# 4_-MCU_POWER.net
KiCad netlist of a schematic drawn in Altium Designer
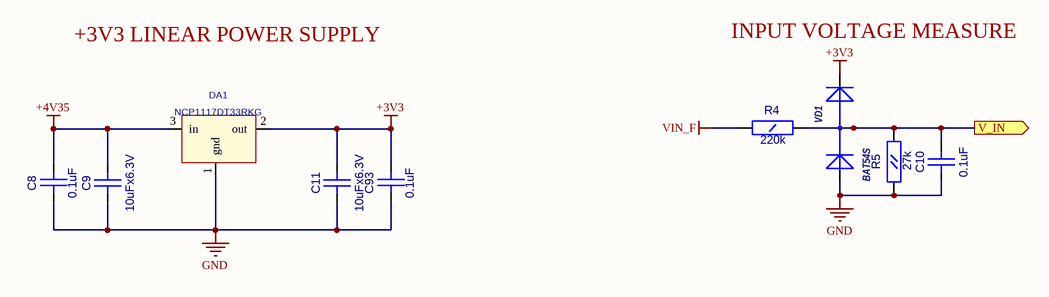
[diagram p0: [4]-MCU_POWER.SchDoc]

(export (version "E")
  (design (tool "Eeschema 10.0.6"))
  (components
    (comp (ref "C8")
      (value "0.1uF")
      (footprint "CC0603")
      (description "CC0603")
      (libsource (lib "gprs_modem_2") (part "CC0603"))
    )
    (comp (ref "C9")
      (value "10uFx6.3V")
      (footprint "CC0805")
      (description "CC0805")
      (libsource (lib "gprs_modem_2") (part "CC0805"))
    )
    (comp (ref "C10")
      (value "0.1uF")
      (footprint "CC0603")
      (description "CC0603")
      (libsource (lib "gprs_modem_2") (part "CC0603"))
    )
    (comp (ref "C11")
      (value "10uFx6.3V")
      (footprint "CC0805")
      (description "CC0805")
      (libsource (lib "gprs_modem_2") (part "CC0805"))
    )
    (comp (ref "C93")
      (value "0.1uF")
      (footprint "CC0603")
      (description "CC0603")
      (libsource (lib "gprs_modem_2") (part "CC0603"))
    )
    (comp (ref "DA1")
      (value "NCP1117DT33RKG")
      (footprint "SOT-223")
      (description "Linear Regulator 3.3V")
      (libsource (lib "fizik_lib") (part "NCP1117DT33RKG"))
    )
    (comp (ref "R4")
      (value "220k")
      (footprint "RC1206")
      (description "RC1206")
      (libsource (lib "fizik_lib") (part "RC1206"))
    )
    (comp (ref "R5")
      (value "27k")
      (footprint "RC0603")
      (description "RC0603")
      (libsource (lib "gprs_modem_2") (part "RC0603"))
    )
    (comp (ref "VD1")
      (value "BAT54S")
      (footprint "SOT-23(GSD)")
      (description "1.0 Ampere General Purpose Rectifier")
      (libsource (lib "gprs_modem_2") (part "BAT54S"))
    )
  )
  (nets
    (net (code "1") (name "+3V3") (class "Default")
      (node (ref "C11") (pin "2") (pinfunction "B_2") (pintype "passive"))
      (node (ref "C93") (pin "1") (pinfunction "A_1") (pintype "passive"))
      (node (ref "DA1") (pin "2") (pinfunction "out_2") (pintype "passive"))
      (node (ref "VD1") (pin "2") (pinfunction "K_2") (pintype "passive"))
    )
    (net (code "2") (name "+4V35") (class "Default")
      (node (ref "C8") (pin "1") (pinfunction "A_1") (pintype "passive"))
      (node (ref "C9") (pin "2") (pinfunction "B_2") (pintype "passive"))
      (node (ref "DA1") (pin "3") (pinfunction "in_3") (pintype "passive"))
    )
    (net (code "3") (name "/V_IN") (class "Default")
      (node (ref "C10") (pin "2") (pinfunction "B_2") (pintype "passive"))
      (node (ref "R4") (pin "2") (pinfunction "B_2") (pintype "passive"))
      (node (ref "R5") (pin "2") (pinfunction "B_2") (pintype "passive"))
      (node (ref "VD1") (pin "3") (pinfunction "AK_3") (pintype "passive"))
    )
    (net (code "4") (name "GND") (class "Default")
      (node (ref "C10") (pin "1") (pinfunction "A_1") (pintype "passive"))
      (node (ref "C11") (pin "1") (pinfunction "A_1") (pintype "passive"))
      (node (ref "C8") (pin "2") (pinfunction "B_2") (pintype "passive"))
      (node (ref "C9") (pin "1") (pinfunction "A_1") (pintype "passive"))
      (node (ref "C93") (pin "2") (pinfunction "B_2") (pintype "passive"))
      (node (ref "DA1") (pin "1") (pinfunction "gnd_1") (pintype "passive"))
      (node (ref "R5") (pin "1") (pinfunction "A_1") (pintype "passive"))
      (node (ref "VD1") (pin "1") (pinfunction "A_1") (pintype "passive"))
    )
    (net (code "5") (name "VIN_F") (class "Default")
      (node (ref "R4") (pin "1") (pinfunction "A_1") (pintype "passive"))
    )
  )
)
